# BUS.net
KiCad netlist of a schematic drawn in Altium Designer
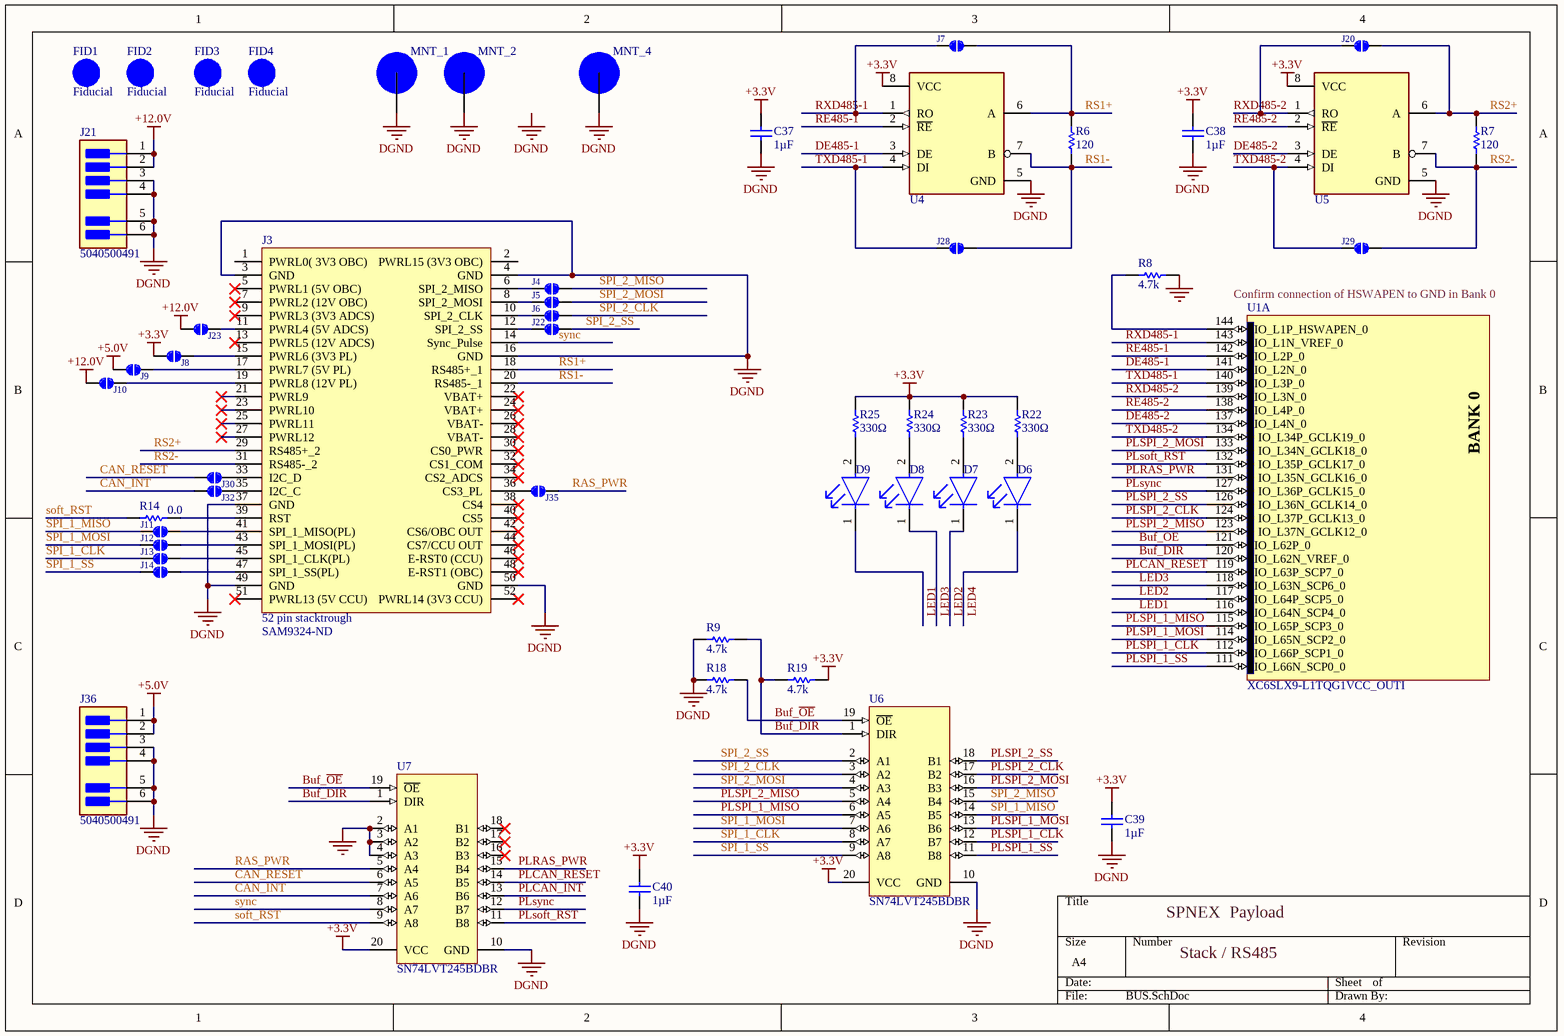
[diagram p0: BUS.SchDoc]

(export (version "E")
  (design (tool "Eeschema 10.0.6"))
  (components
    (comp (ref "C37")
      (value "Cap_CER_1U_10V_0603")
      (footprint "0603CAP")
      (description "Capacitor")
      (fields
        (field (name "MANUFACTURER") "Taiyo Yuden")
        (field (name "MANUFACTURER PART NUMBER") "LMK107B7105KA-T")
        (field (name "CAPACITANCE") "1µF")
      )
      (libsource (lib "SPNeX_NewPL") (part "Cap_CER_1U_10V_0603"))
    )
    (comp (ref "C38")
      (value "Cap_CER_1U_10V_0603")
      (footprint "0603CAP")
      (description "Capacitor")
      (fields
        (field (name "MANUFACTURER") "Taiyo Yuden")
        (field (name "MANUFACTURER PART NUMBER") "LMK107B7105KA-T")
        (field (name "CAPACITANCE") "1µF")
      )
      (libsource (lib "SPNeX_NewPL") (part "Cap_CER_1U_10V_0603"))
    )
    (comp (ref "C39")
      (value "Cap_CER_1U_10V_0603")
      (footprint "0603CAP")
      (description "Capacitor")
      (fields
        (field (name "MANUFACTURER") "Taiyo Yuden")
        (field (name "MANUFACTURER PART NUMBER") "LMK107B7105KA-T")
        (field (name "CAPACITANCE") "1µF")
      )
      (libsource (lib "SPNeX_NewPL") (part "Cap_CER_1U_10V_0603"))
    )
    (comp (ref "C40")
      (value "Cap_CER_1U_10V_0603")
      (footprint "0603CAP")
      (description "Capacitor")
      (fields
        (field (name "MANUFACTURER") "Taiyo Yuden")
        (field (name "MANUFACTURER PART NUMBER") "LMK107B7105KA-T")
        (field (name "CAPACITANCE") "1µF")
      )
      (libsource (lib "SPNeX_NewPL") (part "Cap_CER_1U_10V_0603"))
    )
    (comp (ref "D6")
      (value "LED RED CLEAR 2SMD")
      (footprint "ROHM_SML-21_MFG")
      (description "Red 625nm LED Indication - Discrete 1.8V 0805 (2012 Metric)")
      (fields
        (field (name "MANUFACTURER") "Kingbright")
        (field (name "MANUFACTURER PART NUMBER") "APT2012LSECK/J3-PRV")
      )
      (libsource (lib "SPNeX_NewPL") (part "APT2012LSECK/J3-PRV"))
    )
    (comp (ref "D7")
      (value "LED RED CLEAR 2SMD")
      (footprint "ROHM_SML-21_MFG")
      (description "Red 625nm LED Indication - Discrete 1.8V 0805 (2012 Metric)")
      (fields
        (field (name "MANUFACTURER") "Kingbright")
        (field (name "MANUFACTURER PART NUMBER") "APT2012LSECK/J3-PRV")
      )
      (libsource (lib "SPNeX_NewPL") (part "APT2012LSECK/J3-PRV"))
    )
    (comp (ref "D8")
      (value "LED RED CLEAR 2SMD")
      (footprint "ROHM_SML-21_MFG")
      (description "Red 625nm LED Indication - Discrete 1.8V 0805 (2012 Metric)")
      (fields
        (field (name "MANUFACTURER") "Kingbright")
        (field (name "MANUFACTURER PART NUMBER") "APT2012LSECK/J3-PRV")
      )
      (libsource (lib "SPNeX_NewPL") (part "APT2012LSECK/J3-PRV"))
    )
    (comp (ref "D9")
      (value "LED RED CLEAR 2SMD")
      (footprint "ROHM_SML-21_MFG")
      (description "Red 625nm LED Indication - Discrete 1.8V 0805 (2012 Metric)")
      (fields
        (field (name "MANUFACTURER") "Kingbright")
        (field (name "MANUFACTURER PART NUMBER") "APT2012LSECK/J3-PRV")
      )
      (libsource (lib "SPNeX_NewPL") (part "APT2012LSECK/J3-PRV"))
    )
    (comp (ref "FID1") (value "Fiducial") (footprint "FID") (libsource (lib "SPNeX_NewPL") (part "Fiducial")))
    (comp (ref "FID2") (value "Fiducial") (footprint "FID") (libsource (lib "SPNeX_NewPL") (part "Fiducial")))
    (comp (ref "FID3") (value "Fiducial") (footprint "FID") (libsource (lib "SPNeX_NewPL") (part "Fiducial")))
    (comp (ref "FID4") (value "Fiducial") (footprint "FID") (libsource (lib "SPNeX_NewPL") (part "Fiducial")))
    (comp (ref "J3")
      (value "52 pin stacktrough")
      (footprint "StackThrough52")
      (description "Conn Elevated Socket SKT 52 POS 2.54mm Solder ST Top Entry Thru-Hole Tube")
      (fields
        (field (name "MANUFACTURER") "Samtec")
        (field (name "MANUFACTURER PART NUMBER") "ESQ-126-38-G-D")
        (field (name "SUPPLIER PART NUMBER 1") "SAM9324-ND")
      )
      (libsource (lib "SPNeX_NewPL") (part "SPNEX_BUS"))
    )
    (comp (ref "J4")
      (value "JUMPER")
      (footprint "SJMP")
      (description "OPTION SELECTION PAD")
      (libsource (lib "Spnex_lib") (part "JUMPER"))
    )
    (comp (ref "J5")
      (value "JUMPER")
      (footprint "SJMP")
      (description "OPTION SELECTION PAD")
      (libsource (lib "Spnex_lib") (part "JUMPER"))
    )
    (comp (ref "J6")
      (value "JUMPER")
      (footprint "SJMP")
      (description "OPTION SELECTION PAD")
      (libsource (lib "Spnex_lib") (part "JUMPER"))
    )
    (comp (ref "J7")
      (value "JUMPER")
      (footprint "SJMP")
      (description "OPTION SELECTION PAD")
      (libsource (lib "Kh_Lib") (part "JUMPER"))
    )
    (comp (ref "J8")
      (value "JUMPER")
      (footprint "SJMP")
      (description "OPTION SELECTION PAD")
      (libsource (lib "Spnex_lib") (part "JUMPER"))
    )
    (comp (ref "J9")
      (value "JUMPER")
      (footprint "SJMP")
      (description "OPTION SELECTION PAD")
      (libsource (lib "Spnex_lib") (part "JUMPER"))
    )
    (comp (ref "J10")
      (value "JUMPER")
      (footprint "SJMP")
      (description "OPTION SELECTION PAD")
      (libsource (lib "Spnex_lib") (part "JUMPER"))
    )
    (comp (ref "J11")
      (value "JUMPER")
      (footprint "SJMP")
      (description "OPTION SELECTION PAD")
      (libsource (lib "Spnex_lib") (part "JUMPER"))
    )
    (comp (ref "J12")
      (value "JUMPER")
      (footprint "SJMP")
      (description "OPTION SELECTION PAD")
      (libsource (lib "Spnex_lib") (part "JUMPER"))
    )
    (comp (ref "J13")
      (value "JUMPER")
      (footprint "SJMP")
      (description "OPTION SELECTION PAD")
      (libsource (lib "Spnex_lib") (part "JUMPER"))
    )
    (comp (ref "J14")
      (value "JUMPER")
      (footprint "SJMP")
      (description "OPTION SELECTION PAD")
      (libsource (lib "Spnex_lib") (part "JUMPER"))
    )
    (comp (ref "J20")
      (value "JUMPER")
      (footprint "SJMP")
      (description "OPTION SELECTION PAD")
      (libsource (lib "Kh_Lib") (part "JUMPER"))
    )
    (comp (ref "J21")
      (value "5040500491")
      (footprint "MOLEX_5040500491")
      (description "Connector Header Surface Mount, Right Angle 4 position 0.059\" (1.50mm)")
      (fields (field (name "MANUFACTURER") "Molex"))
      (libsource (lib "Spnex_library") (part "5040500491"))
    )
    (comp (ref "J22")
      (value "JUMPER")
      (footprint "SJMP")
      (description "OPTION SELECTION PAD")
      (libsource (lib "Spnex_lib") (part "JUMPER"))
    )
    (comp (ref "J23")
      (value "JUMPER")
      (footprint "SJMP")
      (description "OPTION SELECTION PAD")
      (libsource (lib "Spnex_lib") (part "JUMPER"))
    )
    (comp (ref "J28")
      (value "JUMPER")
      (footprint "SJMP")
      (description "OPTION SELECTION PAD")
      (libsource (lib "Kh_Lib") (part "JUMPER"))
    )
    (comp (ref "J29")
      (value "JUMPER")
      (footprint "SJMP")
      (description "OPTION SELECTION PAD")
      (libsource (lib "Kh_Lib") (part "JUMPER"))
    )
    (comp (ref "J30")
      (value "JUMPER")
      (footprint "SJMP")
      (description "OPTION SELECTION PAD")
      (libsource (lib "Kh_Lib") (part "JUMPER"))
    )
    (comp (ref "J32")
      (value "JUMPER")
      (footprint "SJMP")
      (description "OPTION SELECTION PAD")
      (libsource (lib "Kh_Lib") (part "JUMPER"))
    )
    (comp (ref "J35")
      (value "JUMPER")
      (footprint "SJMP")
      (description "OPTION SELECTION PAD")
      (libsource (lib "Kh_Lib") (part "JUMPER"))
    )
    (comp (ref "J36")
      (value "5040500491")
      (footprint "MOLEX_5040500491")
      (description "Connector Header Surface Mount, Right Angle 4 position 0.059\" (1.50mm)")
      (fields (field (name "MANUFACTURER") "Molex"))
      (libsource (lib "Spnex_library") (part "5040500491"))
    )
    (comp (ref "MNT_1")
      (value "Mount Hole")
      (footprint "Mount_Hole")
      (libsource (lib "SPNeX_NewPL") (part "MNT_Hole"))
    )
    (comp (ref "MNT_2")
      (value "Mount Hole")
      (footprint "Mount_Hole")
      (libsource (lib "SPNeX_NewPL") (part "MNT_Hole"))
    )
    (comp (ref "MNT_4")
      (value "Mount Hole")
      (footprint "Mount_Hole")
      (libsource (lib "SPNeX_NewPL") (part "MNT_Hole"))
    )
    (comp (ref "R6")
      (value "RES_120_0.25W_0603")
      (footprint "0603RES")
      (description "RES SMD 120 OHM 5% 1/4W 0603")
      (fields
        (field (name "MANUFACTURER") "Rohm Semiconductor")
        (field (name "MANUFACTURER PART NUMBER") "ESR03EZPJ121")
        (field (name "RESISTANCE (OHMS)") "120")
      )
      (libsource (lib "Spnex_lib") (part "RES_120_0.25W_0603"))
    )
    (comp (ref "R7")
      (value "RES_120_0.25W_0603")
      (footprint "0603RES")
      (description "RES SMD 120 OHM 5% 1/4W 0603")
      (fields
        (field (name "MANUFACTURER") "Rohm Semiconductor")
        (field (name "MANUFACTURER PART NUMBER") "ESR03EZPJ121")
        (field (name "RESISTANCE (OHMS)") "120")
      )
      (libsource (lib "Spnex_lib") (part "RES_120_0.25W_0603"))
    )
    (comp (ref "R8")
      (value "RES_4.7K_0.1W_0603")
      (footprint "0603RES")
      (description "Resistor")
      (fields
        (field (name "MANUFACTURER") "Stackpole Electronics Inc.")
        (field (name "MANUFACTURER PART NUMBER") "RMCF0603JT4K70")
        (field (name "RESISTANCE (OHMS)") "4.7k")
      )
      (libsource (lib "SPNeX_NewPL") (part "RES_4.7K_0.1W_0603"))
    )
    (comp (ref "R9")
      (value "RES_4.7K_0.1W_0603")
      (footprint "0603RES")
      (description "Resistor")
      (fields
        (field (name "MANUFACTURER") "Stackpole Electronics Inc.")
        (field (name "MANUFACTURER PART NUMBER") "RMCF0603JT4K70")
        (field (name "RESISTANCE (OHMS)") "4.7k")
      )
      (libsource (lib "SPNeX_NewPL") (part "RES_4.7K_0.1W_0603"))
    )
    (comp (ref "R14")
      (value "RES_0_0.1W_0603")
      (footprint "0603RES")
      (description "Resistor")
      (fields
        (field (name "MANUFACTURER") "Samsung Electro-Mechanics America, Inc.")
        (field (name "MANUFACTURER PART NUMBER") "RC1608J000CS")
        (field (name "RESISTANCE (OHMS)") "0.0")
      )
      (libsource (lib "SPNeX_NewPL") (part "RES_0_0.1W_0603"))
    )
    (comp (ref "R18")
      (value "RES_4.7K_0.1W_0603")
      (footprint "0603RES")
      (description "Resistor")
      (fields
        (field (name "MANUFACTURER") "Stackpole Electronics Inc.")
        (field (name "MANUFACTURER PART NUMBER") "RMCF0603JT4K70")
        (field (name "RESISTANCE (OHMS)") "4.7k")
      )
      (libsource (lib "SPNeX_NewPL") (part "RES_4.7K_0.1W_0603"))
    )
    (comp (ref "R19")
      (value "RES_4.7K_0.1W_0603")
      (footprint "0603RES")
      (description "Resistor")
      (fields
        (field (name "MANUFACTURER") "Stackpole Electronics Inc.")
        (field (name "MANUFACTURER PART NUMBER") "RMCF0603JT4K70")
        (field (name "RESISTANCE (OHMS)") "4.7k")
      )
      (libsource (lib "SPNeX_NewPL") (part "RES_4.7K_0.1W_0603"))
    )
    (comp (ref "R22")
      (value "RES_330 Ohm_0603")
      (footprint "0603")
      (description "Res Thick Film 0603 330 Ohm 5% 0.1W(1/10W) +/-200ppm/ßC Pad SMD Automotive T/R")
      (fields
        (field (name "MANUFACTURER") "Panasonic")
        (field (name "MANUFACTURER PART NUMBER") "ERJ-3GEYJ331V")
        (field (name "RESISTANCE") "330Ω")
      )
      (libsource (lib "Spnex_lib") (part "RES_330 Ohm_0603"))
    )
    (comp (ref "R23")
      (value "RES_330 Ohm_0603")
      (footprint "0603")
      (description "Res Thick Film 0603 330 Ohm 5% 0.1W(1/10W) +/-200ppm/ßC Pad SMD Automotive T/R")
      (fields
        (field (name "MANUFACTURER") "Panasonic")
        (field (name "MANUFACTURER PART NUMBER") "ERJ-3GEYJ331V")
        (field (name "RESISTANCE") "330Ω")
      )
      (libsource (lib "Spnex_lib") (part "RES_330 Ohm_0603"))
    )
    (comp (ref "R24")
      (value "RES_330 Ohm_0603")
      (footprint "0603")
      (description "Res Thick Film 0603 330 Ohm 5% 0.1W(1/10W) +/-200ppm/ßC Pad SMD Automotive T/R")
      (fields
        (field (name "MANUFACTURER") "Panasonic")
        (field (name "MANUFACTURER PART NUMBER") "ERJ-3GEYJ331V")
        (field (name "RESISTANCE") "330Ω")
      )
      (libsource (lib "Spnex_lib") (part "RES_330 Ohm_0603"))
    )
    (comp (ref "R25")
      (value "RES_330 Ohm_0603")
      (footprint "0603")
      (description "Res Thick Film 0603 330 Ohm 5% 0.1W(1/10W) +/-200ppm/ßC Pad SMD Automotive T/R")
      (fields
        (field (name "MANUFACTURER") "Panasonic")
        (field (name "MANUFACTURER PART NUMBER") "ERJ-3GEYJ331V")
        (field (name "RESISTANCE") "330Ω")
      )
      (libsource (lib "Spnex_lib") (part "RES_330 Ohm_0603"))
    )
    (comp (ref "U1")
      (value "XC6SLX9-L1TQG1VCC_OUTI")
      (footprint "TQG144_M")
      (fields (field (name "PUBLISHER") "Altium Limited"))
      (libsource (lib "SPNeX_NewPL") (part "XC6SLX9-L1TQG144I"))
    )
    (comp (ref "U4")
      (value "ADM3493ARZ")
      (footprint "Soic8_IPCA")
      (fields (field (name "MANUFACTURER") "Analog Devices"))
      (libsource (lib "SPNeX_NewPL") (part "ADM3493ARZ"))
    )
    (comp (ref "U5")
      (value "ADM3493ARZ")
      (footprint "Soic8_IPCA")
      (fields (field (name "MANUFACTURER") "Analog Devices"))
      (libsource (lib "SPNeX_NewPL") (part "ADM3493ARZ"))
    )
    (comp (ref "U6")
      (value "SN74LVT245BDBR")
      (footprint "DB0020A_M")
      (description "3.3-V ABT Octal Bus Transceivers With 3-State Outputs, DB0020A, LARGE T&R")
      (fields
        (field (name "GENERIC PART NUMBER") "SN74LVT245B")
        (field (name "MANUFACTURER") "Texas Instruments")
      )
      (libsource (lib "Spnex_lib") (part "SN74LVT245BDBR"))
    )
    (comp (ref "U7")
      (value "SN74LVT245BDBR")
      (footprint "DB0020A_M")
      (description "3.3-V ABT Octal Bus Transceivers With 3-State Outputs, DB0020A, LARGE T&R")
      (fields
        (field (name "GENERIC PART NUMBER") "SN74LVT245B")
        (field (name "MANUFACTURER") "Texas Instruments")
      )
      (libsource (lib "Spnex_library") (part "SN74LVT245BDBR"))
    )
  )
  (nets
    (net (code "1") (name "+3.3V") (class "Default")
      (node (ref "C37") (pin "2") (pinfunction "2_2") (pintype "passive"))
      (node (ref "C38") (pin "2") (pinfunction "2_2") (pintype "passive"))
      (node (ref "C39") (pin "2") (pinfunction "2_2") (pintype "passive"))
      (node (ref "C40") (pin "2") (pinfunction "2_2") (pintype "passive"))
      (node (ref "J8") (pin "1") (pinfunction "1_1") (pintype "passive"))
      (node (ref "R19") (pin "1") (pinfunction "1_1") (pintype "passive"))
      (node (ref "R22") (pin "2") (pinfunction "2_2") (pintype "passive"))
      (node (ref "R23") (pin "2") (pinfunction "2_2") (pintype "passive"))
      (node (ref "R24") (pin "2") (pinfunction "2_2") (pintype "passive"))
      (node (ref "R25") (pin "2") (pinfunction "2_2") (pintype "passive"))
      (node (ref "U4") (pin "8") (pinfunction "VCC_8") (pintype "power_in"))
      (node (ref "U5") (pin "8") (pinfunction "VCC_8") (pintype "power_in"))
      (node (ref "U6") (pin "20") (pinfunction "VCC_20") (pintype "power_in"))
      (node (ref "U7") (pin "20") (pinfunction "VCC_20") (pintype "power_in"))
    )
    (net (code "2") (name "+5.0V") (class "Default")
      (node (ref "J36") (pin "1") (pinfunction "1_1") (pintype "passive"))
      (node (ref "J36") (pin "2") (pinfunction "2_2") (pintype "passive"))
      (node (ref "J9") (pin "1") (pinfunction "1_1") (pintype "passive"))
    )
    (net (code "3") (name "+12.0V") (class "Default")
      (node (ref "J10") (pin "1") (pinfunction "1_1") (pintype "passive"))
      (node (ref "J21") (pin "1") (pinfunction "1_1") (pintype "passive"))
      (node (ref "J21") (pin "2") (pinfunction "2_2") (pintype "passive"))
      (node (ref "J23") (pin "1") (pinfunction "1_1") (pintype "passive"))
    )
    (net (code "4") (name "/Buf_DIR") (class "Default")
      (node (ref "R19") (pin "2") (pinfunction "2_2") (pintype "passive"))
      (node (ref "R9") (pin "1") (pinfunction "1_1") (pintype "passive"))
      (node (ref "U1") (pin "120") (pinfunction "IO_L62N_VREF_0_120") (pintype "bidirectional"))
      (node (ref "U6") (pin "1") (pinfunction "DIR_1") (pintype "input"))
      (node (ref "U7") (pin "1") (pinfunction "DIR_1") (pintype "input"))
    )
    (net (code "5") (name "/Buf_~{OE}") (class "Default")
      (node (ref "R18") (pin "1") (pinfunction "1_1") (pintype "passive"))
      (node (ref "U1") (pin "121") (pinfunction "IO_L62P_0_121") (pintype "bidirectional"))
      (node (ref "U6") (pin "19") (pinfunction "~{OE}_19") (pintype "input"))
      (node (ref "U7") (pin "19") (pinfunction "~{OE}_19") (pintype "input"))
    )
    (net (code "6") (name "/CAN_INT") (class "Default")
      (node (ref "J32") (pin "1") (pinfunction "1_1") (pintype "passive"))
      (node (ref "U7") (pin "7") (pinfunction "A6_7") (pintype "bidirectional"))
    )
    (net (code "7") (name "/CAN_RESET") (class "Default")
      (node (ref "J30") (pin "1") (pinfunction "1_1") (pintype "passive"))
      (node (ref "U7") (pin "6") (pinfunction "A5_6") (pintype "bidirectional"))
    )
    (net (code "8") (name "/DE485-1") (class "Default")
      (node (ref "U1") (pin "141") (pinfunction "IO_L2N_0_141") (pintype "bidirectional"))
      (node (ref "U4") (pin "3") (pinfunction "DE_3") (pintype "input"))
    )
    (net (code "9") (name "/DE485-2") (class "Default")
      (node (ref "U1") (pin "137") (pinfunction "IO_L4N_0_137") (pintype "bidirectional"))
      (node (ref "U5") (pin "3") (pinfunction "DE_3") (pintype "input"))
    )
    (net (code "10") (name "/LED1") (class "Default")
      (node (ref "D9") (pin "1") (pinfunction "C_1") (pintype "passive"))
      (node (ref "U1") (pin "116") (pinfunction "IO_L64N_SCP4_0_116") (pintype "bidirectional"))
    )
    (net (code "11") (name "/LED2") (class "Default")
      (node (ref "D7") (pin "1") (pinfunction "C_1") (pintype "passive"))
      (node (ref "U1") (pin "117") (pinfunction "IO_L64P_SCP5_0_117") (pintype "bidirectional"))
    )
    (net (code "12") (name "/LED3") (class "Default")
      (node (ref "D8") (pin "1") (pinfunction "C_1") (pintype "passive"))
      (node (ref "U1") (pin "118") (pinfunction "IO_L63N_SCP6_0_118") (pintype "bidirectional"))
    )
    (net (code "13") (name "/LED4") (class "Default")
      (node (ref "D6") (pin "1") (pinfunction "C_1") (pintype "passive"))
    )
    (net (code "14") (name "/PLCAN_INT") (class "Default")
      (node (ref "U7") (pin "13") (pinfunction "B6_13") (pintype "bidirectional"))
    )
    (net (code "15") (name "/PLCAN_RESET") (class "Default")
      (node (ref "U1") (pin "119") (pinfunction "IO_L63P_SCP7_0_119") (pintype "bidirectional"))
      (node (ref "U7") (pin "14") (pinfunction "B5_14") (pintype "bidirectional"))
    )
    (net (code "16") (name "/PLRAS_PWR") (class "Default")
      (node (ref "U1") (pin "131") (pinfunction "IO_L35N_GCLK16_0_131") (pintype "bidirectional"))
      (node (ref "U7") (pin "15") (pinfunction "B4_15") (pintype "bidirectional"))
    )
    (net (code "17") (name "/PLSPI_1_CLK") (class "Default")
      (node (ref "U1") (pin "112") (pinfunction "IO_L66P_SCP1_0_112") (pintype "bidirectional"))
      (node (ref "U6") (pin "12") (pinfunction "B7_12") (pintype "bidirectional"))
    )
    (net (code "18") (name "/PLSPI_1_MISO") (class "Default")
      (node (ref "U1") (pin "115") (pinfunction "IO_L65P_SCP3_0_115") (pintype "bidirectional"))
      (node (ref "U6") (pin "6") (pinfunction "A5_6") (pintype "bidirectional"))
    )
    (net (code "19") (name "/PLSPI_1_MOSI") (class "Default")
      (node (ref "U1") (pin "114") (pinfunction "IO_L65N_SCP2_0_114") (pintype "bidirectional"))
      (node (ref "U6") (pin "13") (pinfunction "B6_13") (pintype "bidirectional"))
    )
    (net (code "20") (name "/PLSPI_1_SS") (class "Default")
      (node (ref "U1") (pin "111") (pinfunction "IO_L66N_SCP0_0_111") (pintype "bidirectional"))
      (node (ref "U6") (pin "11") (pinfunction "B8_11") (pintype "bidirectional"))
    )
    (net (code "21") (name "/PLSPI_2_CLK") (class "Default")
      (node (ref "U1") (pin "124") (pinfunction "IO_L37P_GCLK13_0_124") (pintype "bidirectional"))
      (node (ref "U6") (pin "17") (pinfunction "B2_17") (pintype "bidirectional"))
    )
    (net (code "22") (name "/PLSPI_2_MISO") (class "Default")
      (node (ref "U1") (pin "123") (pinfunction "IO_L37N_GCLK12_0_123") (pintype "bidirectional"))
      (node (ref "U6") (pin "5") (pinfunction "A4_5") (pintype "bidirectional"))
    )
    (net (code "23") (name "/PLSPI_2_MOSI") (class "Default")
      (node (ref "U1") (pin "133") (pinfunction "IO_L34N_GCLK18_0_133") (pintype "bidirectional"))
      (node (ref "U6") (pin "16") (pinfunction "B3_16") (pintype "bidirectional"))
    )
    (net (code "24") (name "/PLSPI_2_SS") (class "Default")
      (node (ref "U1") (pin "126") (pinfunction "IO_L36N_GCLK14_0_126") (pintype "bidirectional"))
      (node (ref "U6") (pin "18") (pinfunction "B1_18") (pintype "bidirectional"))
    )
    (net (code "25") (name "/PLsoft_RST") (class "Default")
      (node (ref "U1") (pin "132") (pinfunction "IO_L35P_GCLK17_0_132") (pintype "bidirectional"))
      (node (ref "U7") (pin "11") (pinfunction "B8_11") (pintype "bidirectional"))
    )
    (net (code "26") (name "/PLsync") (class "Default")
      (node (ref "U1") (pin "127") (pinfunction "IO_L36P_GCLK15_0_127") (pintype "bidirectional"))
      (node (ref "U7") (pin "12") (pinfunction "B7_12") (pintype "bidirectional"))
    )
    (net (code "27") (name "/RAS_PWR") (class "Default")
      (node (ref "J35") (pin "2") (pinfunction "2_2") (pintype "passive"))
      (node (ref "U7") (pin "5") (pinfunction "A4_5") (pintype "bidirectional"))
    )
    (net (code "28") (name "/RS1+") (class "Default")
      (node (ref "J3") (pin "18") (pinfunction "RS485+_1_18") (pintype "passive"))
      (node (ref "J7") (pin "2") (pinfunction "2_2") (pintype "passive"))
      (node (ref "R6") (pin "2") (pinfunction "2_2") (pintype "passive"))
      (node (ref "U4") (pin "6") (pinfunction "A_6") (pintype "passive"))
    )
    (net (code "29") (name "/RS1-") (class "Default")
      (node (ref "J28") (pin "2") (pinfunction "2_2") (pintype "passive"))
      (node (ref "J3") (pin "20") (pinfunction "RS485-_1_20") (pintype "passive"))
      (node (ref "R6") (pin "1") (pinfunction "1_1") (pintype "passive"))
      (node (ref "U4") (pin "7") (pinfunction "B_7") (pintype "passive"))
    )
    (net (code "30") (name "/RS2+") (class "Default")
      (node (ref "J20") (pin "2") (pinfunction "2_2") (pintype "passive"))
      (node (ref "J3") (pin "29") (pinfunction "RS485+_2_29") (pintype "passive"))
      (node (ref "R7") (pin "2") (pinfunction "2_2") (pintype "passive"))
      (node (ref "U5") (pin "6") (pinfunction "A_6") (pintype "passive"))
    )
    (net (code "31") (name "/RS2-") (class "Default")
      (node (ref "J29") (pin "2") (pinfunction "2_2") (pintype "passive"))
      (node (ref "J3") (pin "31") (pinfunction "RS485-_2_31") (pintype "passive"))
      (node (ref "R7") (pin "1") (pinfunction "1_1") (pintype "passive"))
      (node (ref "U5") (pin "7") (pinfunction "B_7") (pintype "passive"))
    )
    (net (code "32") (name "/RXD485-1") (class "Default")
      (node (ref "J7") (pin "1") (pinfunction "1_1") (pintype "passive"))
      (node (ref "U1") (pin "143") (pinfunction "IO_L1N_VREF_0_143") (pintype "bidirectional"))
      (node (ref "U4") (pin "1") (pinfunction "RO_1") (pintype "output"))
    )
    (net (code "33") (name "/RXD485-2") (class "Default")
      (node (ref "J20") (pin "1") (pinfunction "1_1") (pintype "passive"))
      (node (ref "U1") (pin "139") (pinfunction "IO_L3N_0_139") (pintype "bidirectional"))
      (node (ref "U5") (pin "1") (pinfunction "RO_1") (pintype "output"))
    )
    (net (code "34") (name "/SPI_1_CLK") (class "Default")
      (node (ref "J13") (pin "1") (pinfunction "1_1") (pintype "passive"))
      (node (ref "U6") (pin "8") (pinfunction "A7_8") (pintype "bidirectional"))
    )
    (net (code "35") (name "/SPI_1_MISO") (class "Default")
      (node (ref "J11") (pin "1") (pinfunction "1_1") (pintype "passive"))
      (node (ref "U6") (pin "14") (pinfunction "B5_14") (pintype "bidirectional"))
    )
    (net (code "36") (name "/SPI_1_MOSI") (class "Default")
      (node (ref "J12") (pin "1") (pinfunction "1_1") (pintype "passive"))
      (node (ref "U6") (pin "7") (pinfunction "A6_7") (pintype "bidirectional"))
    )
    (net (code "37") (name "/SPI_1_SS") (class "Default")
      (node (ref "J14") (pin "1") (pinfunction "1_1") (pintype "passive"))
      (node (ref "U6") (pin "9") (pinfunction "A8_9") (pintype "bidirectional"))
    )
    (net (code "38") (name "/SPI_2_CLK") (class "Default")
      (node (ref "J6") (pin "2") (pinfunction "2_2") (pintype "passive"))
      (node (ref "U6") (pin "3") (pinfunction "A2_3") (pintype "bidirectional"))
    )
    (net (code "39") (name "/SPI_2_MISO") (class "Default")
      (node (ref "J4") (pin "2") (pinfunction "2_2") (pintype "passive"))
      (node (ref "U6") (pin "15") (pinfunction "B4_15") (pintype "bidirectional"))
    )
    (net (code "40") (name "/SPI_2_MOSI") (class "Default")
      (node (ref "J5") (pin "2") (pinfunction "2_2") (pintype "passive"))
      (node (ref "U6") (pin "4") (pinfunction "A3_4") (pintype "bidirectional"))
    )
    (net (code "41") (name "/SPI_2_SS") (class "Default")
      (node (ref "J22") (pin "2") (pinfunction "2_2") (pintype "passive"))
      (node (ref "U6") (pin "2") (pinfunction "A1_2") (pintype "bidirectional"))
    )
    (net (code "42") (name "/TXD485-1") (class "Default")
      (node (ref "J28") (pin "1") (pinfunction "1_1") (pintype "passive"))
      (node (ref "U1") (pin "140") (pinfunction "IO_L3P_0_140") (pintype "bidirectional"))
      (node (ref "U4") (pin "4") (pinfunction "DI_4") (pintype "input"))
    )
    (net (code "43") (name "/TXD485-2") (class "Default")
      (node (ref "J29") (pin "1") (pinfunction "1_1") (pintype "passive"))
      (node (ref "U1") (pin "134") (pinfunction "IO_L34P_GCLK19_0_134") (pintype "bidirectional"))
      (node (ref "U5") (pin "4") (pinfunction "DI_4") (pintype "input"))
    )
    (net (code "44") (name "/soft_RST") (class "Default")
      (node (ref "R14") (pin "1") (pinfunction "1_1") (pintype "passive"))
      (node (ref "U7") (pin "9") (pinfunction "A8_9") (pintype "bidirectional"))
    )
    (net (code "45") (name "/sync") (class "Default")
      (node (ref "J3") (pin "14") (pinfunction "Sync_Pulse_14") (pintype "passive"))
      (node (ref "U7") (pin "8") (pinfunction "A7_8") (pintype "bidirectional"))
    )
    (net (code "46") (name "/~{RE}485-1") (class "Default")
      (node (ref "U1") (pin "142") (pinfunction "IO_L2P_0_142") (pintype "bidirectional"))
      (node (ref "U4") (pin "2") (pinfunction "~{RE}_2") (pintype "input"))
    )
    (net (code "47") (name "/~{RE}485-2") (class "Default")
      (node (ref "U1") (pin "138") (pinfunction "IO_L4P_0_138") (pintype "bidirectional"))
      (node (ref "U5") (pin "2") (pinfunction "~{RE}_2") (pintype "input"))
    )
    (net (code "48") (name "DGND") (class "Default")
      (node (ref "C37") (pin "1") (pinfunction "1_1") (pintype "passive"))
      (node (ref "C38") (pin "1") (pinfunction "1_1") (pintype "passive"))
      (node (ref "C39") (pin "1") (pinfunction "1_1") (pintype "passive"))
      (node (ref "C40") (pin "1") (pinfunction "1_1") (pintype "passive"))
      (node (ref "J21") (pin "3") (pinfunction "3_3") (pintype "passive"))
      (node (ref "J21") (pin "4") (pinfunction "4_4") (pintype "passive"))
      (node (ref "J21") (pin "5") (pinfunction "5_5") (pintype "passive"))
      (node (ref "J21") (pin "6") (pinfunction "6_6") (pintype "passive"))
      (node (ref "J3") (pin "16") (pinfunction "GND_16") (pintype "passive"))
      (node (ref "J3") (pin "3") (pinfunction "GND_3") (pintype "passive"))
      (node (ref "J3") (pin "37") (pinfunction "GND_37") (pintype "passive"))
      (node (ref "J3") (pin "4") (pinfunction "GND_4") (pintype "passive"))
      (node (ref "J3") (pin "49") (pinfunction "GND_49") (pintype "passive"))
      (node (ref "J3") (pin "50") (pinfunction "GND_50") (pintype "passive"))
      (node (ref "J36") (pin "3") (pinfunction "3_3") (pintype "passive"))
      (node (ref "J36") (pin "4") (pinfunction "4_4") (pintype "passive"))
      (node (ref "J36") (pin "5") (pinfunction "5_5") (pintype "passive"))
      (node (ref "J36") (pin "6") (pinfunction "6_6") (pintype "passive"))
      (node (ref "MNT_1") (pin "1") (pinfunction "1_1") (pintype "passive"))
      (node (ref "MNT_2") (pin "1") (pinfunction "1_1") (pintype "passive"))
      (node (ref "MNT_4") (pin "1") (pinfunction "1_1") (pintype "passive"))
      (node (ref "R18") (pin "2") (pinfunction "2_2") (pintype "passive"))
      (node (ref "R8") (pin "2") (pinfunction "2_2") (pintype "passive"))
      (node (ref "R9") (pin "2") (pinfunction "2_2") (pintype "passive"))
      (node (ref "U4") (pin "5") (pinfunction "GND_5") (pintype "power_in"))
      (node (ref "U5") (pin "5") (pinfunction "GND_5") (pintype "power_in"))
      (node (ref "U6") (pin "10") (pinfunction "GND_10") (pintype "power_in"))
      (node (ref "U7") (pin "10") (pinfunction "GND_10") (pintype "power_in"))
      (node (ref "U7") (pin "2") (pinfunction "A1_2") (pintype "bidirectional"))
      (node (ref "U7") (pin "3") (pinfunction "A2_3") (pintype "bidirectional"))
      (node (ref "U7") (pin "4") (pinfunction "A3_4") (pintype "bidirectional"))
    )
    (net (code "49") (name "Net-(D6-A)") (class "Default")
      (node (ref "D6") (pin "2") (pinfunction "A_2") (pintype "passive"))
      (node (ref "R22") (pin "1") (pinfunction "1_1") (pintype "passive"))
    )
    (net (code "50") (name "Net-(D7-A)") (class "Default")
      (node (ref "D7") (pin "2") (pinfunction "A_2") (pintype "passive"))
      (node (ref "R23") (pin "1") (pinfunction "1_1") (pintype "passive"))
    )
    (net (code "51") (name "Net-(D8-A)") (class "Default")
      (node (ref "D8") (pin "2") (pinfunction "A_2") (pintype "passive"))
      (node (ref "R24") (pin "1") (pinfunction "1_1") (pintype "passive"))
    )
    (net (code "52") (name "Net-(D9-A)") (class "Default")
      (node (ref "D9") (pin "2") (pinfunction "A_2") (pintype "passive"))
      (node (ref "R25") (pin "1") (pinfunction "1_1") (pintype "passive"))
    )
    (net (code "53") (name "Net-(J3-CS3_PL)") (class "Default")
      (node (ref "J3") (pin "36") (pinfunction "CS3_PL_36") (pintype "passive"))
      (node (ref "J35") (pin "1") (pinfunction "1_1") (pintype "passive"))
    )
    (net (code "54") (name "Net-(J3-I2C_C)") (class "Default")
      (node (ref "J3") (pin "35") (pinfunction "I2C_C_35") (pintype "passive"))
      (node (ref "J32") (pin "2") (pinfunction "2_2") (pintype "passive"))
    )
    (net (code "55") (name "Net-(J3-I2C_D)") (class "Default")
      (node (ref "J3") (pin "33") (pinfunction "I2C_D_33") (pintype "passive"))
      (node (ref "J30") (pin "2") (pinfunction "2_2") (pintype "passive"))
    )
    (net (code "56") (name "Net-(J3-PWRL4_(5V_ADCS))") (class "Default")
      (node (ref "J23") (pin "2") (pinfunction "2_2") (pintype "passive"))
      (node (ref "J3") (pin "11") (pinfunction "PWRL4_(5V_ADCS)_11") (pintype "passive"))
    )
    (net (code "57") (name "Net-(J3-PWRL6_(3V3_PL))") (class "Default")
      (node (ref "J3") (pin "15") (pinfunction "PWRL6_(3V3_PL)_15") (pintype "passive"))
      (node (ref "J8") (pin "2") (pinfunction "2_2") (pintype "passive"))
    )
    (net (code "58") (name "Net-(J3-PWRL7_(5V_PL))") (class "Default")
      (node (ref "J3") (pin "17") (pinfunction "PWRL7_(5V_PL)_17") (pintype "passive"))
      (node (ref "J9") (pin "2") (pinfunction "2_2") (pintype "passive"))
    )
    (net (code "59") (name "Net-(J3-PWRL8_(12V_PL))") (class "Default")
      (node (ref "J10") (pin "2") (pinfunction "2_2") (pintype "passive"))
      (node (ref "J3") (pin "19") (pinfunction "PWRL8_(12V_PL)_19") (pintype "passive"))
    )
    (net (code "60") (name "Net-(J3-RST)") (class "Default")
      (node (ref "J3") (pin "39") (pinfunction "RST_39") (pintype "passive"))
      (node (ref "R14") (pin "2") (pinfunction "2_2") (pintype "passive"))
    )
    (net (code "61") (name "Net-(J3-SPI_1_CLK(PL))") (class "Default")
      (node (ref "J13") (pin "2") (pinfunction "2_2") (pintype "passive"))
      (node (ref "J3") (pin "45") (pinfunction "SPI_1_CLK(PL)_45") (pintype "passive"))
    )
    (net (code "62") (name "Net-(J3-SPI_1_MISO(PL))") (class "Default")
      (node (ref "J11") (pin "2") (pinfunction "2_2") (pintype "passive"))
      (node (ref "J3") (pin "41") (pinfunction "SPI_1_MISO(PL)_41") (pintype "passive"))
    )
    (net (code "63") (name "Net-(J3-SPI_1_MOSI(PL))") (class "Default")
      (node (ref "J12") (pin "2") (pinfunction "2_2") (pintype "passive"))
      (node (ref "J3") (pin "43") (pinfunction "SPI_1_MOSI(PL)_43") (pintype "passive"))
    )
    (net (code "64") (name "Net-(J3-SPI_1_SS(PL))") (class "Default")
      (node (ref "J14") (pin "2") (pinfunction "2_2") (pintype "passive"))
      (node (ref "J3") (pin "47") (pinfunction "SPI_1_SS(PL)_47") (pintype "passive"))
    )
    (net (code "65") (name "Net-(J3-SPI_2_CLK)") (class "Default")
      (node (ref "J3") (pin "10") (pinfunction "SPI_2_CLK_10") (pintype "passive"))
      (node (ref "J6") (pin "1") (pinfunction "1_1") (pintype "passive"))
    )
    (net (code "66") (name "Net-(J3-SPI_2_MISO)") (class "Default")
      (node (ref "J3") (pin "6") (pinfunction "SPI_2_MISO_6") (pintype "passive"))
      (node (ref "J4") (pin "1") (pinfunction "1_1") (pintype "passive"))
    )
    (net (code "67") (name "Net-(J3-SPI_2_MOSI)") (class "Default")
      (node (ref "J3") (pin "8") (pinfunction "SPI_2_MOSI_8") (pintype "passive"))
      (node (ref "J5") (pin "1") (pinfunction "1_1") (pintype "passive"))
    )
    (net (code "68") (name "Net-(J3-SPI_2_SS)") (class "Default")
      (node (ref "J22") (pin "1") (pinfunction "1_1") (pintype "passive"))
      (node (ref "J3") (pin "12") (pinfunction "SPI_2_SS_12") (pintype "passive"))
    )
    (net (code "69") (name "Net-(U1A-IO_L1P_HSWAPEN_0)") (class "Default")
      (node (ref "R8") (pin "1") (pinfunction "1_1") (pintype "passive"))
      (node (ref "U1") (pin "144") (pinfunction "IO_L1P_HSWAPEN_0_144") (pintype "bidirectional"))
    )
    (net (code "70") (name "unconnected-(J3-CS0_PWR-Pad30)") (class "Default")
      (node (ref "J3") (pin "30") (pinfunction "CS0_PWR_30") (pintype "passive+no_connect"))
    )
    (net (code "71") (name "unconnected-(J3-CS1_COM-Pad32)") (class "Default")
      (node (ref "J3") (pin "32") (pinfunction "CS1_COM_32") (pintype "passive+no_connect"))
    )
    (net (code "72") (name "unconnected-(J3-CS2_ADCS-Pad34)") (class "Default")
      (node (ref "J3") (pin "34") (pinfunction "CS2_ADCS_34") (pintype "passive+no_connect"))
    )
    (net (code "73") (name "unconnected-(J3-CS4-Pad38)") (class "Default")
      (node (ref "J3") (pin "38") (pinfunction "CS4_38") (pintype "passive+no_connect"))
    )
    (net (code "74") (name "unconnected-(J3-CS5-Pad40)") (class "Default")
      (node (ref "J3") (pin "40") (pinfunction "CS5_40") (pintype "passive+no_connect"))
    )
    (net (code "75") (name "unconnected-(J3-CS6{slash}OBC_OUT-Pad42)") (class "Default")
      (node (ref "J3") (pin "42") (pinfunction "CS6/OBC_OUT_42") (pintype "passive+no_connect"))
    )
    (net (code "76") (name "unconnected-(J3-CS7{slash}CCU_OUT-Pad44)") (class "Default")
      (node (ref "J3") (pin "44") (pinfunction "CS7/CCU_OUT_44") (pintype "passive+no_connect"))
    )
    (net (code "77") (name "unconnected-(J3-E-RST0_(CCU)-Pad46)") (class "Default")
      (node (ref "J3") (pin "46") (pinfunction "E-RST0_(CCU)_46") (pintype "passive+no_connect"))
    )
    (net (code "78") (name "unconnected-(J3-E-RST1_(OBC)-Pad48)") (class "Default")
      (node (ref "J3") (pin "48") (pinfunction "E-RST1_(OBC)_48") (pintype "passive+no_connect"))
    )
    (net (code "79") (name "unconnected-(J3-PWRL0(_3V3_OBC)-Pad1)") (class "Default")
      (node (ref "J3") (pin "1") (pinfunction "PWRL0(_3V3_OBC)_1") (pintype "passive"))
    )
    (net (code "80") (name "unconnected-(J3-PWRL1_(5V_OBC)-Pad5)") (class "Default")
      (node (ref "J3") (pin "5") (pinfunction "PWRL1_(5V_OBC)_5") (pintype "passive+no_connect"))
    )
    (net (code "81") (name "unconnected-(J3-PWRL2_(12V_OBC)-Pad7)") (class "Default")
      (node (ref "J3") (pin "7") (pinfunction "PWRL2_(12V_OBC)_7") (pintype "passive+no_connect"))
    )
    (net (code "82") (name "unconnected-(J3-PWRL3_(3V3_ADCS)-Pad9)") (class "Default")
      (node (ref "J3") (pin "9") (pinfunction "PWRL3_(3V3_ADCS)_9") (pintype "passive+no_connect"))
    )
    (net (code "83") (name "unconnected-(J3-PWRL5_(12V_ADCS)-Pad13)") (class "Default")
      (node (ref "J3") (pin "13") (pinfunction "PWRL5_(12V_ADCS)_13") (pintype "passive+no_connect"))
    )
    (net (code "84") (name "unconnected-(J3-PWRL9-Pad21)") (class "Default")
      (node (ref "J3") (pin "21") (pinfunction "PWRL9_21") (pintype "passive+no_connect"))
    )
    (net (code "85") (name "unconnected-(J3-PWRL10-Pad23)") (class "Default")
      (node (ref "J3") (pin "23") (pinfunction "PWRL10_23") (pintype "passive+no_connect"))
    )
    (net (code "86") (name "unconnected-(J3-PWRL11-Pad25)") (class "Default")
      (node (ref "J3") (pin "25") (pinfunction "PWRL11_25") (pintype "passive+no_connect"))
    )
    (net (code "87") (name "unconnected-(J3-PWRL12-Pad27)") (class "Default")
      (node (ref "J3") (pin "27") (pinfunction "PWRL12_27") (pintype "passive+no_connect"))
    )
    (net (code "88") (name "unconnected-(J3-PWRL13_(5V_CCU)-Pad51)") (class "Default")
      (node (ref "J3") (pin "51") (pinfunction "PWRL13_(5V_CCU)_51") (pintype "passive+no_connect"))
    )
    (net (code "89") (name "unconnected-(J3-PWRL14_(3V3_CCU)-Pad52)") (class "Default")
      (node (ref "J3") (pin "52") (pinfunction "PWRL14_(3V3_CCU)_52") (pintype "passive+no_connect"))
    )
    (net (code "90") (name "unconnected-(J3-PWRL15_(3V3_OBC)-Pad2)") (class "Default")
      (node (ref "J3") (pin "2") (pinfunction "PWRL15_(3V3_OBC)_2") (pintype "passive"))
    )
    (net (code "91") (name "unconnected-(J3-VBAT+-Pad22)") (class "Default")
      (node (ref "J3") (pin "22") (pinfunction "VBAT+_22") (pintype "passive+no_connect"))
    )
    (net (code "92") (name "unconnected-(J3-VBAT+-Pad24)") (class "Default")
      (node (ref "J3") (pin "24") (pinfunction "VBAT+_24") (pintype "passive+no_connect"))
    )
    (net (code "93") (name "unconnected-(J3-VBAT--Pad26)") (class "Default")
      (node (ref "J3") (pin "26") (pinfunction "VBAT-_26") (pintype "passive+no_connect"))
    )
    (net (code "94") (name "unconnected-(J3-VBAT--Pad28)") (class "Default")
      (node (ref "J3") (pin "28") (pinfunction "VBAT-_28") (pintype "passive+no_connect"))
    )
    (net (code "95") (name "unconnected-(U7-B1-Pad18)") (class "Default")
      (node (ref "U7") (pin "18") (pinfunction "B1_18") (pintype "bidirectional+no_connect"))
    )
    (net (code "96") (name "unconnected-(U7-B2-Pad17)") (class "Default")
      (node (ref "U7") (pin "17") (pinfunction "B2_17") (pintype "bidirectional+no_connect"))
    )
    (net (code "97") (name "unconnected-(U7-B3-Pad16)") (class "Default")
      (node (ref "U7") (pin "16") (pinfunction "B3_16") (pintype "bidirectional+no_connect"))
    )
  )
)
